# comutator.net
KiCad netlist of a schematic drawn in Altium Designer
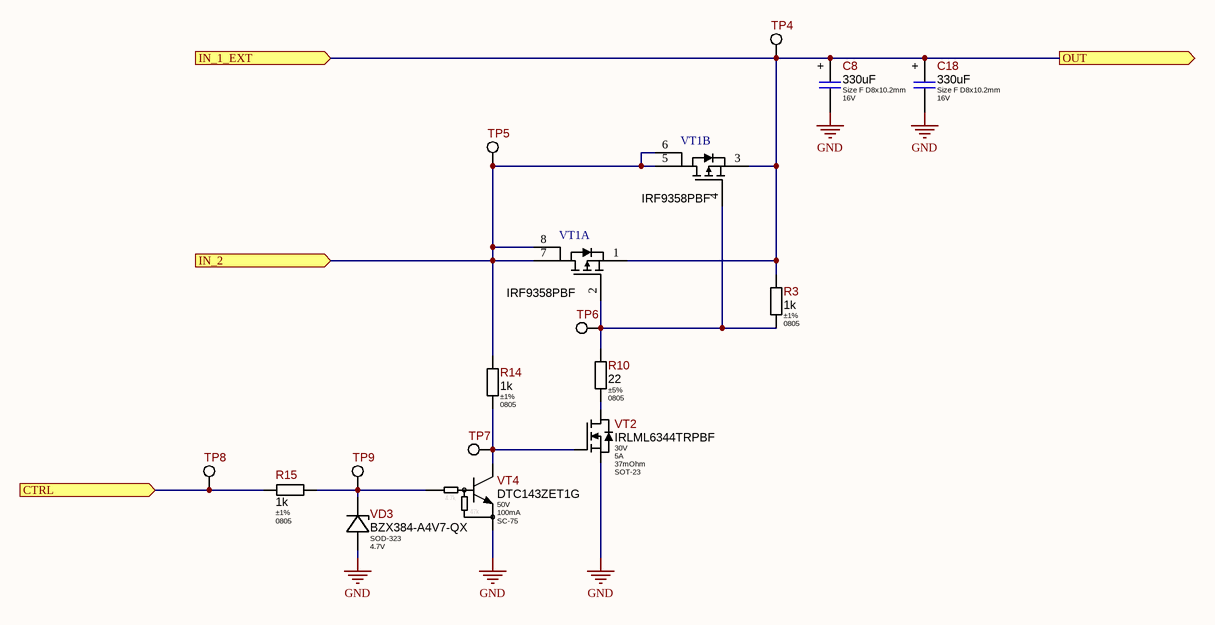
[diagram p0: comutator.SchDoc]

(export (version "E")
  (design (tool "Eeschema 10.0.6"))
  (components
    (comp (ref "C8")
      (value "330uF")
      (footprint "CAP-AE-830x1020H30_MED")
      (fields
        (field (name "PACKAGE") "Size F D8x10.2mm")
        (field (name "VOLTAGE") "16V")
        (field (name "PART NUMBER") "EEEFK1C331P")
        (field (name "MANUFACTURER") "Panasonic")
        (field (name "TOLERANCE") "±20%")
      )
      (libsource (lib "vitech_capacitors") (part "EEE-1HA330AP"))
    )
    (comp (ref "C18")
      (value "330uF")
      (footprint "CAP-AE-830x1020H30_MED")
      (fields
        (field (name "PACKAGE") "Size F D8x10.2mm")
        (field (name "VOLTAGE") "16V")
        (field (name "PART NUMBER") "EEEFK1C331P")
        (field (name "MANUFACTURER") "Panasonic")
        (field (name "TOLERANCE") "±20%")
      )
      (libsource (lib "vitech_capacitors") (part "EEE-1HA330AP"))
    )
    (comp (ref "R3")
      (value "1k")
      (footprint "R_ANY_CHIP_0805_MED")
      (description "2.2 kOhms ±1% 1/8W 0805 Thick Film Resistor")
      (fields
        (field (name "TOLERANCE") "±1%")
        (field (name "PACKAGE") "0805")
        (field (name "PART NUMBER") "RC0805FR-072K2L")
        (field (name "MANUFACTURER") "Yageo")
      )
      (libsource (lib "resistors") (part "RC0805FR-072K2L"))
    )
    (comp (ref "R10")
      (value "22")
      (footprint "R_ANY_CHIP_0805_MED")
      (description "22 Ohms ±5%, 1/8W 0805 Thick Film Resistor")
      (fields
        (field (name "TOLERANCE") "±5%")
        (field (name "PACKAGE") "0805")
        (field (name "PART NUMBER") "RC0805JR-0722RL")
        (field (name "MANUFACTURER") "Yageo")
      )
      (libsource (lib "resistors") (part "RC0805JR-0722RL"))
    )
    (comp (ref "R14")
      (value "1k")
      (footprint "R_ANY_CHIP_0805_MED")
      (description "2.2 kOhms ±1% 1/8W 0805 Thick Film Resistor")
      (fields
        (field (name "TOLERANCE") "±1%")
        (field (name "PACKAGE") "0805")
        (field (name "PART NUMBER") "RC0805FR-072K2L")
        (field (name "MANUFACTURER") "Yageo")
      )
      (libsource (lib "resistors") (part "RC0805FR-072K2L"))
    )
    (comp (ref "R15")
      (value "1k")
      (footprint "R_ANY_CHIP_0805_MED")
      (description "2.2 kOhms ±1% 1/8W 0805 Thick Film Resistor")
      (fields
        (field (name "TOLERANCE") "±1%")
        (field (name "PACKAGE") "0805")
        (field (name "PART NUMBER") "RC0805FR-072K2L")
        (field (name "MANUFACTURER") "Yageo")
      )
      (libsource (lib "resistors") (part "RC0805FR-072K2L"))
    )
    (comp (ref "TP4")
      (value "PAD-0.96mm")
      (footprint "PAD-0.96mm")
      (description "0.96mm Pad for Plug-In or Receptacle")
      (fields (field (name "MANUFACTURER") "NONE"))
      (libsource (lib "probetools") (part "PAD-0.96mm"))
    )
    (comp (ref "TP5")
      (value "PAD-0.96mm")
      (footprint "PAD-0.96mm")
      (description "0.96mm Pad for Plug-In or Receptacle")
      (fields (field (name "MANUFACTURER") "NONE"))
      (libsource (lib "probetools") (part "PAD-0.96mm"))
    )
    (comp (ref "TP6")
      (value "PAD-0.96mm")
      (footprint "PAD-0.96mm")
      (description "0.96mm Pad for Plug-In or Receptacle")
      (fields (field (name "MANUFACTURER") "NONE"))
      (libsource (lib "probetools") (part "PAD-0.96mm"))
    )
    (comp (ref "TP7")
      (value "PAD-0.96mm")
      (footprint "PAD-0.96mm")
      (description "0.96mm Pad for Plug-In or Receptacle")
      (fields (field (name "MANUFACTURER") "NONE"))
      (libsource (lib "probetools") (part "PAD-0.96mm"))
    )
    (comp (ref "TP8")
      (value "PAD-0.96mm")
      (footprint "PAD-0.96mm")
      (description "0.96mm Pad for Plug-In or Receptacle")
      (fields (field (name "MANUFACTURER") "NONE"))
      (libsource (lib "probetools") (part "PAD-0.96mm"))
    )
    (comp (ref "TP9")
      (value "PAD-0.96mm")
      (footprint "PAD-0.96mm")
      (description "0.96mm Pad for Plug-In or Receptacle")
      (fields (field (name "MANUFACTURER") "NONE"))
      (libsource (lib "probetools") (part "PAD-0.96mm"))
    )
    (comp (ref "VD3")
      (value "BZX384-A4V7-QX")
      (footprint "SOD-323_MED")
      (description "Zener Diode 4.7V, 300mW, ±1%, Leakage 3uA @ 2V, SOD-323")
      (fields
        (field (name "PART NUMBER") "BZX384-A4V7-QX")
        (field (name "PACKAGE") "SOD-323")
        (field (name "VOLTAGE") "4.7V")
        (field (name "MANUFACTURER") "Nexperia USA")
      )
      (libsource (lib "vitech_semiconductors") (part "BZX384-A4V7-QX"))
    )
    (comp (ref "VT1")
      (value "IRF9358PBF")
      (footprint "SOIC-8")
      (description "MOSFET 2P-CH 30V 9.2A 8SOIC")
      (fields
        (field (name "MANUFACTURER") "Infineon Technologies")
        (field (name "OCTOPART") "https://octopart.com/irf9358pbf-infineon-65873752")
        (field (name "MANUFACTURER PART NUMBER") "IRF9358PBF")
      )
      (libsource (lib "vitech_semiconductors") (part "IRF9358PbF"))
    )
    (comp (ref "VT2")
      (value "IRLML6344")
      (footprint "SOT-23_MED")
      (description "30V, 5A max N-Channel HEXFET MOSFET, 29mOhm @ Vgs = 4.5V")
      (fields
        (field (name "PART NUMBER") "IRLML6344TRPBF")
        (field (name "VDS") "30V")
        (field (name "ID") "5A")
        (field (name "RDS") "37mOhm")
        (field (name "PACKAGE") "SOT-23")
        (field (name "MANUFACTURER") "Infineon Technologies")
      )
      (libsource (lib "transistors") (part "IRLML6344TRPBF"))
    )
    (comp (ref "VT4")
      (value "DTC143ZET1G")
      (footprint "SOT-416")
      (description "50V, 100mA Low Vce(sat) NPN Digital Transistor, Pre-Biased 4.7k/47k (with built-in resistors)")
      (fields
        (field (name "PART NUMBER") "DTC143ZET1G")
        (field (name "VCE") "50V")
        (field (name "IC") "100mA")
        (field (name "PACKAGE") "SC-75")
        (field (name "MANUFACTURER") "Onsemi")
      )
      (libsource (lib "vitech_semiconductors") (part "DTC143ZET1G"))
    )
  )
  (nets
    (net (code "1") (name "/CTRL") (class "Default")
      (node (ref "R15") (pin "1") (pintype "passive"))
      (node (ref "TP8") (pin "1") (pintype "passive"))
    )
    (net (code "2") (name "/IN_1_EXT") (class "Default")
      (node (ref "C18") (pin "1") (pinfunction "1_1") (pintype "passive"))
      (node (ref "C8") (pin "1") (pinfunction "1_1") (pintype "passive"))
      (node (ref "R3") (pin "1") (pintype "passive"))
      (node (ref "TP4") (pin "1") (pintype "passive"))
      (node (ref "VT1") (pin "1") (pinfunction "S2_1") (pintype "passive"))
      (node (ref "VT1") (pin "3") (pinfunction "S1_3") (pintype "passive"))
    )
    (net (code "3") (name "/IN_2") (class "Default")
      (node (ref "R14") (pin "1") (pintype "passive"))
      (node (ref "TP5") (pin "1") (pintype "passive"))
      (node (ref "VT1") (pin "5") (pinfunction "D12_5") (pintype "passive"))
      (node (ref "VT1") (pin "6") (pinfunction "D11_6") (pintype "passive"))
      (node (ref "VT1") (pin "7") (pinfunction "D22_7") (pintype "passive"))
      (node (ref "VT1") (pin "8") (pinfunction "D21_8") (pintype "passive"))
    )
    (net (code "4") (name "GND") (class "Default")
      (node (ref "C18") (pin "2") (pinfunction "2_2") (pintype "passive"))
      (node (ref "C8") (pin "2") (pinfunction "2_2") (pintype "passive"))
      (node (ref "VD3") (pin "AN") (pintype "passive"))
      (node (ref "VT2") (pin "2") (pinfunction "S_2") (pintype "passive"))
      (node (ref "VT4") (pin "2") (pinfunction "E_2") (pintype "passive"))
    )
    (net (code "5") (name "Net-(VT1A-G2)") (class "Default")
      (node (ref "R10") (pin "1") (pintype "passive"))
      (node (ref "R3") (pin "2") (pintype "passive"))
      (node (ref "TP6") (pin "1") (pintype "passive"))
      (node (ref "VT1") (pin "2") (pinfunction "G2_2") (pintype "passive"))
      (node (ref "VT1") (pin "4") (pinfunction "G1_4") (pintype "passive"))
    )
    (net (code "6") (name "Net-(VT2-D)") (class "Default")
      (node (ref "R10") (pin "2") (pintype "passive"))
      (node (ref "VT2") (pin "3") (pinfunction "D_3") (pintype "passive"))
    )
    (net (code "7") (name "Net-(VT2-G)") (class "Default")
      (node (ref "R14") (pin "2") (pintype "passive"))
      (node (ref "TP7") (pin "1") (pintype "passive"))
      (node (ref "VT2") (pin "1") (pinfunction "G_1") (pintype "passive"))
      (node (ref "VT4") (pin "3") (pinfunction "C_3") (pintype "passive"))
    )
    (net (code "8") (name "Net-(VT4-B)") (class "Default")
      (node (ref "R15") (pin "2") (pintype "passive"))
      (node (ref "TP9") (pin "1") (pintype "passive"))
      (node (ref "VD3") (pin "CA") (pintype "passive"))
      (node (ref "VT4") (pin "1") (pinfunction "B_1") (pintype "passive"))
    )
  )
)
